# main_board.net
KiCad netlist of a schematic drawn in EAGLE
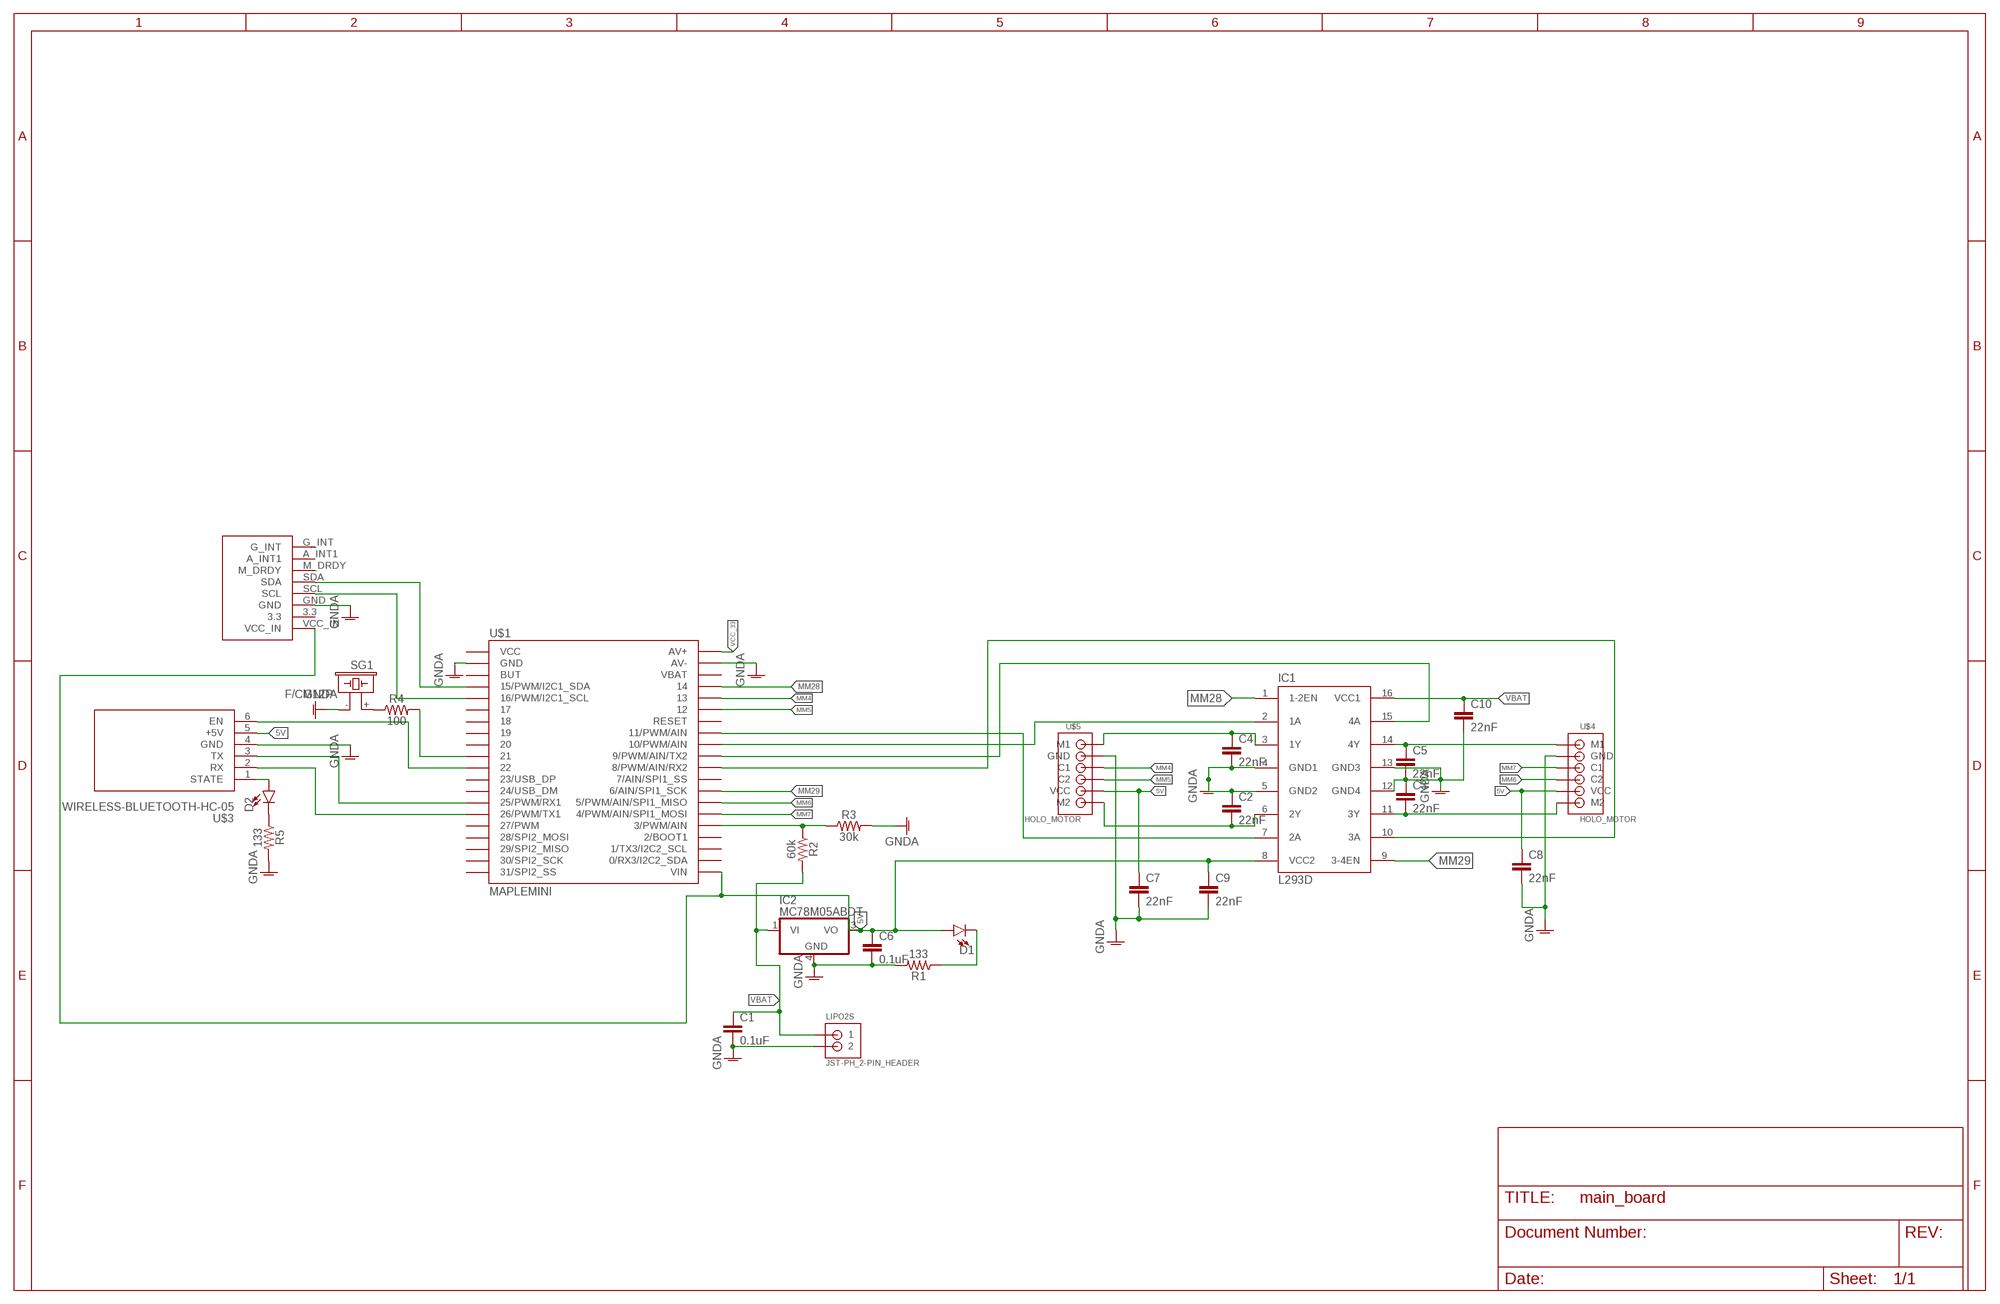
[diagram p0: schematic, sheet 1]

(export (version "E")
  (design (tool "Eeschema 10.0.6"))
  (components
    (comp (ref "C1")
      (value "0.1uF")
      (footprint "eagle-import:0603")
      (libsource (lib "eagle-import") (part "0.1UF-0603-25V-(+80/-20%)"))
    )
    (comp (ref "C2")
      (value "22nF")
      (footprint "eagle-import:0603")
      (libsource (lib "eagle-import") (part "22NF/22,000PF-0603-50V-10%"))
    )
    (comp (ref "C3")
      (value "22nF")
      (footprint "eagle-import:0603")
      (libsource (lib "eagle-import") (part "22NF/22,000PF-0603-50V-10%"))
    )
    (comp (ref "C4")
      (value "22nF")
      (footprint "eagle-import:0603")
      (libsource (lib "eagle-import") (part "22NF/22,000PF-0603-50V-10%"))
    )
    (comp (ref "C5")
      (value "22nF")
      (footprint "eagle-import:0603")
      (libsource (lib "eagle-import") (part "22NF/22,000PF-0603-50V-10%"))
    )
    (comp (ref "C6")
      (value "0.1uF")
      (footprint "eagle-import:0603")
      (libsource (lib "eagle-import") (part "0.1UF-0603-25V-(+80/-20%)"))
    )
    (comp (ref "C7")
      (value "22nF")
      (footprint "eagle-import:0603")
      (fields (field (name "PROD_ID") "CAP-07885"))
      (libsource (lib "eagle-import") (part "22NF/22,000PF-0603-50V-10%"))
    )
    (comp (ref "C8")
      (value "22nF")
      (footprint "eagle-import:0603")
      (fields (field (name "PROD_ID") "CAP-07885"))
      (libsource (lib "eagle-import") (part "22NF/22,000PF-0603-50V-10%"))
    )
    (comp (ref "C9")
      (value "22nF")
      (footprint "eagle-import:0603")
      (fields (field (name "PROD_ID") "CAP-07885"))
      (libsource (lib "eagle-import") (part "22NF/22,000PF-0603-50V-10%"))
    )
    (comp (ref "C10")
      (value "22nF")
      (footprint "eagle-import:0603")
      (fields (field (name "PROD_ID") "CAP-07885"))
      (libsource (lib "eagle-import") (part "22NF/22,000PF-0603-50V-10%"))
    )
    (comp (ref "D1")
      (value "LED-FKIT-1206")
      (footprint "eagle-import:FKIT-LED-1206")
      (libsource (lib "eagle-import") (part "LED-FKIT-1206"))
    )
    (comp (ref "D2")
      (value "LED-FKIT-1206")
      (footprint "eagle-import:FKIT-LED-1206")
      (libsource (lib "eagle-import") (part "LED-FKIT-1206"))
    )
    (comp (ref "IC1")
      (value "L293D")
      (footprint "eagle-import:DIL16")
      (libsource (lib "eagle-import") (part "L293D"))
    )
    (comp (ref "IC2")
      (value "MC78M05ABDT")
      (footprint "eagle-import:DPACK_3")
      (libsource (lib "eagle-import") (part "MC78M05ABDT"))
    )
    (comp (ref "LIPO2S")
      (value "JST-PH_2-PIN_HEADER")
      (footprint "eagle-import:JST_B2B-PH_HEADER")
      (libsource (lib "eagle-import") (part "JST-PH_2-PIN_HEADER"))
    )
    (comp (ref "R1")
      (value "133")
      (footprint "eagle-import:0603")
      (libsource (lib "eagle-import") (part "0.27OHM-0603-1/10W-1%"))
    )
    (comp (ref "R2")
      (value "60k")
      (footprint "eagle-import:0603")
      (libsource (lib "eagle-import") (part "0.27OHM-0603-1/10W-1%"))
    )
    (comp (ref "R3")
      (value "30k")
      (footprint "eagle-import:0603")
      (libsource (lib "eagle-import") (part "0.27OHM-0603-1/10W-1%"))
    )
    (comp (ref "R4")
      (value "100")
      (footprint "eagle-import:0603")
      (libsource (lib "eagle-import") (part "0.27OHM-0603-1/10W-1%"))
    )
    (comp (ref "R5")
      (value "133")
      (footprint "eagle-import:0603")
      (libsource (lib "eagle-import") (part "0.27OHM-0603-1/10W-1%"))
    )
    (comp (ref "SG1")
      (value "F/CM12P")
      (footprint "eagle-import:F_CM12P")
      (libsource (lib "eagle-import") (part "F/CM12P"))
    )
    (comp (ref "U$1")
      (value "MAPLEMINI")
      (footprint "eagle-import:20-DIP")
      (libsource (lib "eagle-import") (part "MAPLEMINI"))
    )
    (comp (ref "U$3")
      (value "WIRELESS-BLUETOOTH-HC-05")
      (footprint "eagle-import:WIRELESS-BLUETOOTH-HC-05")
      (libsource (lib "eagle-import") (part "WIRELESS-BLUETOOTH-HC-05"))
    )
    (comp (ref "U$4")
      (value "HOLO_MOTOR")
      (footprint "eagle-import:HOLO_MOTOR")
      (libsource (lib "eagle-import") (part "HOLO_MOTOR"))
    )
    (comp (ref "U$5")
      (value "HOLO_MOTOR")
      (footprint "eagle-import:HOLO_MOTOR")
      (libsource (lib "eagle-import") (part "HOLO_MOTOR"))
    )
    (comp (ref "U$6")
      (value "GY-85")
      (footprint "eagle-import:GY-85")
      (libsource (lib "eagle-import") (part "GY-85"))
    )
  )
  (nets
    (net (code "1") (name "5V") (class "Default")
      (node (ref "C6") (pin "1") (pinfunction "1_1") (pintype "passive"))
      (node (ref "C7") (pin "1") (pinfunction "1_1") (pintype "passive"))
      (node (ref "C8") (pin "1") (pinfunction "1_1") (pintype "passive"))
      (node (ref "C9") (pin "1") (pinfunction "1_1") (pintype "passive"))
      (node (ref "D1") (pin "A") (pinfunction "A_A") (pintype "passive"))
      (node (ref "IC1") (pin "8") (pinfunction "VCC2_8") (pintype "power_in"))
      (node (ref "IC2") (pin "3") (pinfunction "VO_3") (pintype "passive"))
      (node (ref "U$1") (pin "21") (pinfunction "VIN_21") (pintype "bidirectional"))
      (node (ref "U$3") (pin "5") (pinfunction "+5V_5") (pintype "power_in"))
      (node (ref "U$4") (pin "5") (pinfunction "VCC_5") (pintype "bidirectional"))
      (node (ref "U$5") (pin "5") (pinfunction "VCC_5") (pintype "bidirectional"))
      (node (ref "U$6") (pin "VCC_IN") (pinfunction "VCC_IN_VCC_IN") (pintype "bidirectional"))
    )
    (net (code "2") (name "GNDA") (class "Default")
      (node (ref "C1") (pin "2") (pinfunction "2_2") (pintype "passive"))
      (node (ref "C10") (pin "2") (pinfunction "2_2") (pintype "passive"))
      (node (ref "C2") (pin "1") (pinfunction "1_1") (pintype "passive"))
      (node (ref "C3") (pin "1") (pinfunction "1_1") (pintype "passive"))
      (node (ref "C4") (pin "2") (pinfunction "2_2") (pintype "passive"))
      (node (ref "C5") (pin "2") (pinfunction "2_2") (pintype "passive"))
      (node (ref "C6") (pin "2") (pinfunction "2_2") (pintype "passive"))
      (node (ref "C7") (pin "2") (pinfunction "2_2") (pintype "passive"))
      (node (ref "C8") (pin "2") (pinfunction "2_2") (pintype "passive"))
      (node (ref "C9") (pin "2") (pinfunction "2_2") (pintype "passive"))
      (node (ref "IC1") (pin "12") (pinfunction "GND4_12") (pintype "power_in"))
      (node (ref "IC1") (pin "13") (pinfunction "GND3_13") (pintype "power_in"))
      (node (ref "IC1") (pin "4") (pinfunction "GND1_4") (pintype "power_in"))
      (node (ref "IC1") (pin "5") (pinfunction "GND2_5") (pintype "power_in"))
      (node (ref "IC2") (pin "4") (pinfunction "GND_4") (pintype "passive"))
      (node (ref "LIPO2S") (pin "P2") (pinfunction "2_P2") (pintype "bidirectional"))
      (node (ref "R1") (pin "2") (pinfunction "2_2") (pintype "passive"))
      (node (ref "R3") (pin "2") (pinfunction "2_2") (pintype "passive"))
      (node (ref "R5") (pin "2") (pinfunction "2_2") (pintype "passive"))
      (node (ref "SG1") (pin "-") (pinfunction "2_-") (pintype "passive"))
      (node (ref "U$1") (pin "2") (pinfunction "GND_2") (pintype "bidirectional"))
      (node (ref "U$1") (pin "39") (pinfunction "AV-_39") (pintype "bidirectional"))
      (node (ref "U$3") (pin "4") (pinfunction "GND_4") (pintype "power_in"))
      (node (ref "U$4") (pin "2") (pinfunction "GND_2") (pintype "bidirectional"))
      (node (ref "U$5") (pin "2") (pinfunction "GND_2") (pintype "bidirectional"))
      (node (ref "U$6") (pin "GND") (pinfunction "GND_GND") (pintype "bidirectional"))
    )
    (net (code "3") (name "MM4") (class "Default")
      (node (ref "U$1") (pin "36") (pinfunction "13_36") (pintype "bidirectional"))
      (node (ref "U$5") (pin "3") (pinfunction "C1_3") (pintype "bidirectional"))
    )
    (net (code "4") (name "MM5") (class "Default")
      (node (ref "U$1") (pin "35") (pinfunction "12_35") (pintype "bidirectional"))
      (node (ref "U$5") (pin "4") (pinfunction "C2_4") (pintype "bidirectional"))
    )
    (net (code "5") (name "MM6") (class "Default")
      (node (ref "U$1") (pin "27") (pinfunction "5/PWM/AIN/SPI1_MISO_27") (pintype "bidirectional"))
      (node (ref "U$4") (pin "4") (pinfunction "C2_4") (pintype "bidirectional"))
    )
    (net (code "6") (name "MM7") (class "Default")
      (node (ref "U$1") (pin "26") (pinfunction "4/PWM/AIN/SPI1_MOSI_26") (pintype "bidirectional"))
      (node (ref "U$4") (pin "3") (pinfunction "C1_3") (pintype "bidirectional"))
    )
    (net (code "7") (name "MM28") (class "Default")
      (node (ref "IC1") (pin "1") (pinfunction "1-2EN_1") (pintype "input"))
      (node (ref "U$1") (pin "37") (pinfunction "14_37") (pintype "bidirectional"))
    )
    (net (code "8") (name "MM29") (class "Default")
      (node (ref "IC1") (pin "9") (pinfunction "3-4EN_9") (pintype "input"))
      (node (ref "U$1") (pin "28") (pinfunction "6/AIN/SPI1_SCK_28") (pintype "bidirectional"))
    )
    (net (code "9") (name "Net-(D1-PadC)") (class "Default")
      (node (ref "D1") (pin "C") (pinfunction "C_C") (pintype "passive"))
      (node (ref "R1") (pin "1") (pinfunction "1_1") (pintype "passive"))
    )
    (net (code "10") (name "Net-(D2-PadC)") (class "Default")
      (node (ref "D2") (pin "C") (pinfunction "C_C") (pintype "passive"))
      (node (ref "R5") (pin "1") (pinfunction "1_1") (pintype "passive"))
    )
    (net (code "11") (name "Net-(IC1-1A)") (class "Default")
      (node (ref "IC1") (pin "2") (pinfunction "1A_2") (pintype "input"))
      (node (ref "U$1") (pin "32") (pinfunction "10/PWM/AIN_32") (pintype "bidirectional"))
    )
    (net (code "12") (name "Net-(IC1-1Y)") (class "Default")
      (node (ref "C4") (pin "1") (pinfunction "1_1") (pintype "passive"))
      (node (ref "IC1") (pin "3") (pinfunction "1Y_3") (pintype "output"))
      (node (ref "U$5") (pin "1") (pinfunction "M1_1") (pintype "bidirectional"))
    )
    (net (code "13") (name "Net-(IC1-2A)") (class "Default")
      (node (ref "IC1") (pin "7") (pinfunction "2A_7") (pintype "input"))
      (node (ref "U$1") (pin "33") (pinfunction "11/PWM/AIN_33") (pintype "bidirectional"))
    )
    (net (code "14") (name "Net-(IC1-2Y)") (class "Default")
      (node (ref "C2") (pin "2") (pinfunction "2_2") (pintype "passive"))
      (node (ref "IC1") (pin "6") (pinfunction "2Y_6") (pintype "output"))
      (node (ref "U$5") (pin "6") (pinfunction "M2_6") (pintype "bidirectional"))
    )
    (net (code "15") (name "Net-(IC1-3A)") (class "Default")
      (node (ref "IC1") (pin "10") (pinfunction "3A_10") (pintype "input"))
      (node (ref "U$1") (pin "30") (pinfunction "8/PWM/AIN/RX2_30") (pintype "bidirectional"))
    )
    (net (code "16") (name "Net-(IC1-3Y)") (class "Default")
      (node (ref "C3") (pin "2") (pinfunction "2_2") (pintype "passive"))
      (node (ref "IC1") (pin "11") (pinfunction "3Y_11") (pintype "output"))
      (node (ref "U$4") (pin "6") (pinfunction "M2_6") (pintype "bidirectional"))
    )
    (net (code "17") (name "Net-(IC1-4A)") (class "Default")
      (node (ref "IC1") (pin "15") (pinfunction "4A_15") (pintype "input"))
      (node (ref "U$1") (pin "31") (pinfunction "9/PWM/AIN/TX2_31") (pintype "bidirectional"))
    )
    (net (code "18") (name "Net-(IC1-4Y)") (class "Default")
      (node (ref "C5") (pin "1") (pinfunction "1_1") (pintype "passive"))
      (node (ref "IC1") (pin "14") (pinfunction "4Y_14") (pintype "output"))
      (node (ref "U$4") (pin "1") (pinfunction "M1_1") (pintype "bidirectional"))
    )
    (net (code "19") (name "Net-(SG1-1)") (class "Default")
      (node (ref "R4") (pin "1") (pinfunction "1_1") (pintype "passive"))
      (node (ref "SG1") (pin "+") (pinfunction "1_+") (pintype "passive"))
    )
    (net (code "20") (name "Net-(U$1-3{slash}PWM{slash}AIN)") (class "Default")
      (node (ref "R2") (pin "1") (pinfunction "1_1") (pintype "passive"))
      (node (ref "R3") (pin "1") (pinfunction "1_1") (pintype "passive"))
      (node (ref "U$1") (pin "25") (pinfunction "3/PWM/AIN_25") (pintype "bidirectional"))
    )
    (net (code "21") (name "Net-(U$1-15{slash}PWM{slash}I2C1_SDA)") (class "Default")
      (node (ref "U$1") (pin "4") (pinfunction "15/PWM/I2C1_SDA_4") (pintype "bidirectional"))
      (node (ref "U$6") (pin "SDA") (pinfunction "SDA_SDA") (pintype "bidirectional"))
    )
    (net (code "22") (name "Net-(U$1-16{slash}PWM{slash}I2C1_SCL)") (class "Default")
      (node (ref "U$1") (pin "5") (pinfunction "16/PWM/I2C1_SCL_5") (pintype "bidirectional"))
      (node (ref "U$6") (pin "SCL") (pinfunction "SCL_SCL") (pintype "bidirectional"))
    )
    (net (code "23") (name "Net-(U$1-21)") (class "Default")
      (node (ref "R4") (pin "2") (pinfunction "2_2") (pintype "passive"))
      (node (ref "U$1") (pin "10") (pinfunction "21_10") (pintype "bidirectional"))
    )
    (net (code "24") (name "Net-(U$1-22)") (class "Default")
      (node (ref "U$1") (pin "11") (pinfunction "22_11") (pintype "bidirectional"))
      (node (ref "U$3") (pin "6") (pinfunction "EN_6") (pintype "bidirectional"))
    )
    (net (code "25") (name "Net-(U$1-25{slash}PWM{slash}RX1)") (class "Default")
      (node (ref "U$1") (pin "14") (pinfunction "25/PWM/RX1_14") (pintype "bidirectional"))
      (node (ref "U$3") (pin "3") (pinfunction "TX_3") (pintype "bidirectional"))
    )
    (net (code "26") (name "Net-(U$1-26{slash}PWM{slash}TX1)") (class "Default")
      (node (ref "U$1") (pin "15") (pinfunction "26/PWM/TX1_15") (pintype "bidirectional"))
      (node (ref "U$3") (pin "2") (pinfunction "RX_2") (pintype "bidirectional"))
    )
    (net (code "27") (name "Net-(U$3-STATE)") (class "Default")
      (node (ref "D2") (pin "A") (pinfunction "A_A") (pintype "passive"))
      (node (ref "U$3") (pin "1") (pinfunction "STATE_1") (pintype "bidirectional"))
    )
    (net (code "28") (name "VBAT") (class "Default")
      (node (ref "C1") (pin "1") (pinfunction "1_1") (pintype "passive"))
      (node (ref "C10") (pin "1") (pinfunction "1_1") (pintype "passive"))
      (node (ref "IC1") (pin "16") (pinfunction "VCC1_16") (pintype "power_in"))
      (node (ref "IC2") (pin "1") (pinfunction "VI_1") (pintype "input"))
      (node (ref "LIPO2S") (pin "P1") (pinfunction "1_P1") (pintype "bidirectional"))
      (node (ref "R2") (pin "2") (pinfunction "2_2") (pintype "passive"))
    )
    (net (code "29") (name "VCC_33") (class "Default")
      (node (ref "U$1") (pin "40") (pinfunction "AV+_40") (pintype "bidirectional"))
    )
    (net (code "30") (name "unconnected-(U$1-0{slash}RX3{slash}I2C2_SDA-Pad22)") (class "Default")
      (node (ref "U$1") (pin "22") (pinfunction "0/RX3/I2C2_SDA_22") (pintype "bidirectional"))
    )
    (net (code "31") (name "unconnected-(U$1-1{slash}TX3{slash}I2C2_SCL-Pad23)") (class "Default")
      (node (ref "U$1") (pin "23") (pinfunction "1/TX3/I2C2_SCL_23") (pintype "bidirectional"))
    )
    (net (code "32") (name "unconnected-(U$1-2{slash}BOOT1-Pad24)") (class "Default")
      (node (ref "U$1") (pin "24") (pinfunction "2/BOOT1_24") (pintype "bidirectional"))
    )
    (net (code "33") (name "unconnected-(U$1-7{slash}AIN{slash}SPI1_SS-Pad29)") (class "Default")
      (node (ref "U$1") (pin "29") (pinfunction "7/AIN/SPI1_SS_29") (pintype "bidirectional"))
    )
    (net (code "34") (name "unconnected-(U$1-17-Pad6)") (class "Default")
      (node (ref "U$1") (pin "6") (pinfunction "17_6") (pintype "bidirectional"))
    )
    (net (code "35") (name "unconnected-(U$1-18-Pad7)") (class "Default")
      (node (ref "U$1") (pin "7") (pinfunction "18_7") (pintype "bidirectional"))
    )
    (net (code "36") (name "unconnected-(U$1-19-Pad8)") (class "Default")
      (node (ref "U$1") (pin "8") (pinfunction "19_8") (pintype "bidirectional"))
    )
    (net (code "37") (name "unconnected-(U$1-20-Pad9)") (class "Default")
      (node (ref "U$1") (pin "9") (pinfunction "20_9") (pintype "bidirectional"))
    )
    (net (code "38") (name "unconnected-(U$1-23{slash}USB_DP-Pad12)") (class "Default")
      (node (ref "U$1") (pin "12") (pinfunction "23/USB_DP_12") (pintype "bidirectional"))
    )
    (net (code "39") (name "unconnected-(U$1-24{slash}USB_DM-Pad13)") (class "Default")
      (node (ref "U$1") (pin "13") (pinfunction "24/USB_DM_13") (pintype "bidirectional"))
    )
    (net (code "40") (name "unconnected-(U$1-27{slash}PWM-Pad16)") (class "Default")
      (node (ref "U$1") (pin "16") (pinfunction "27/PWM_16") (pintype "bidirectional"))
    )
    (net (code "41") (name "unconnected-(U$1-28{slash}SPI2_MOSI-Pad17)") (class "Default")
      (node (ref "U$1") (pin "17") (pinfunction "28/SPI2_MOSI_17") (pintype "bidirectional"))
    )
    (net (code "42") (name "unconnected-(U$1-29{slash}SPI2_MISO-Pad18)") (class "Default")
      (node (ref "U$1") (pin "18") (pinfunction "29/SPI2_MISO_18") (pintype "bidirectional"))
    )
    (net (code "43") (name "unconnected-(U$1-30{slash}SPI2_SCK-Pad19)") (class "Default")
      (node (ref "U$1") (pin "19") (pinfunction "30/SPI2_SCK_19") (pintype "bidirectional"))
    )
    (net (code "44") (name "unconnected-(U$1-31{slash}SPI2_SS-Pad20)") (class "Default")
      (node (ref "U$1") (pin "20") (pinfunction "31/SPI2_SS_20") (pintype "bidirectional"))
    )
    (net (code "45") (name "unconnected-(U$1-BUT-Pad3)") (class "Default")
      (node (ref "U$1") (pin "3") (pinfunction "BUT_3") (pintype "bidirectional"))
    )
    (net (code "46") (name "unconnected-(U$1-RESET-Pad34)") (class "Default")
      (node (ref "U$1") (pin "34") (pinfunction "RESET_34") (pintype "bidirectional"))
    )
    (net (code "47") (name "unconnected-(U$1-VBAT-Pad38)") (class "Default")
      (node (ref "U$1") (pin "38") (pinfunction "VBAT_38") (pintype "bidirectional"))
    )
    (net (code "48") (name "unconnected-(U$1-VCC-Pad1)") (class "Default")
      (node (ref "U$1") (pin "1") (pinfunction "VCC_1") (pintype "bidirectional"))
    )
    (net (code "49") (name "unconnected-(U$6-Pad3.3)") (class "Default")
      (node (ref "U$6") (pin "3.3") (pinfunction "3.3_3.3") (pintype "bidirectional"))
    )
    (net (code "50") (name "unconnected-(U$6-PadA_INT1)") (class "Default")
      (node (ref "U$6") (pin "A_INT1") (pinfunction "A_INT1_A_INT1") (pintype "bidirectional"))
    )
    (net (code "51") (name "unconnected-(U$6-PadG_INT)") (class "Default")
      (node (ref "U$6") (pin "G_INT") (pinfunction "G_INT_G_INT") (pintype "bidirectional"))
    )
    (net (code "52") (name "unconnected-(U$6-PadM_DRDY)") (class "Default")
      (node (ref "U$6") (pin "M_DRDY") (pinfunction "M_DRDY_M_DRDY") (pintype "bidirectional"))
    )
  )
)
